# Nodo_actuador_doble.net
KiCad netlist of a schematic drawn in EAGLE
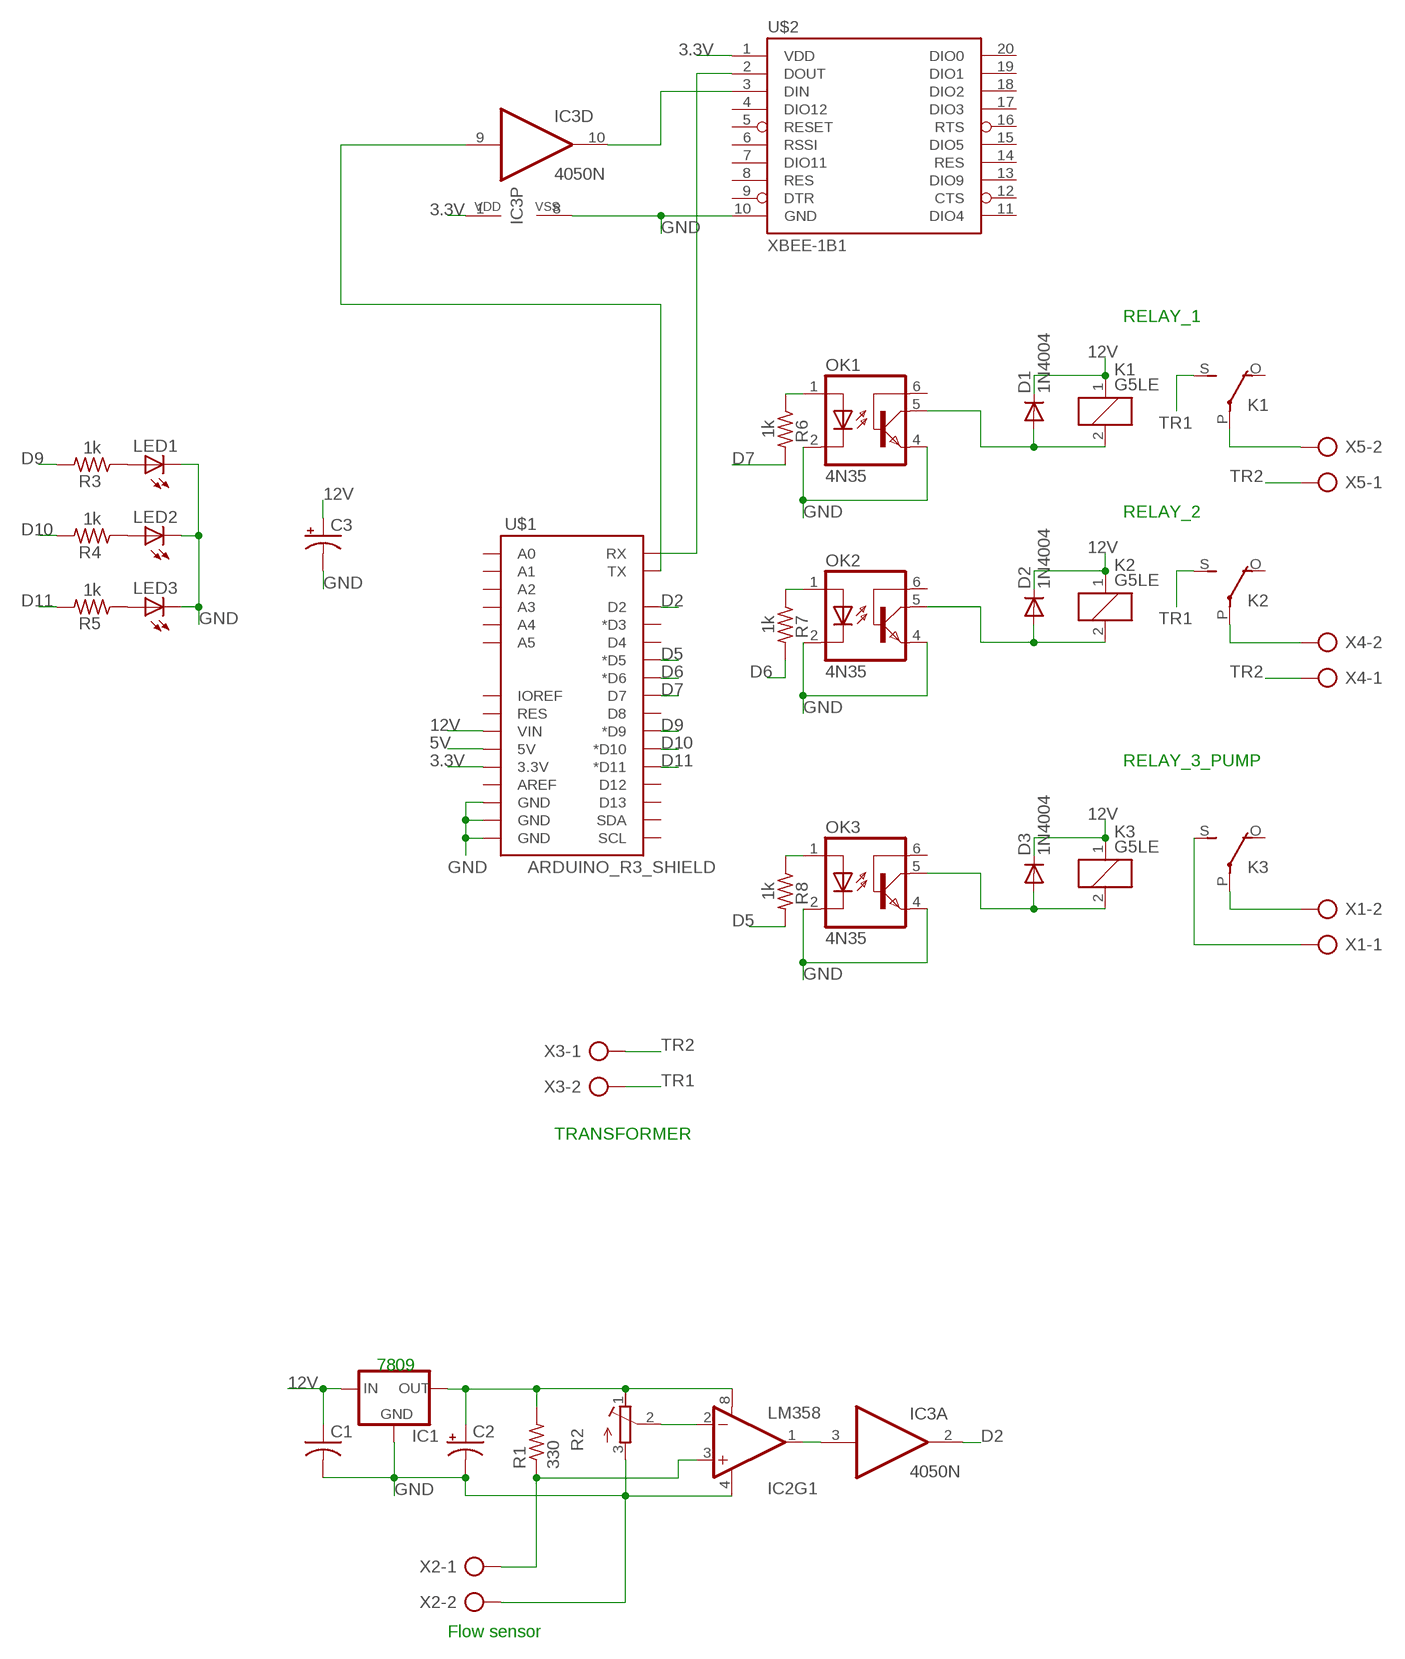
[diagram p0: schematic, sheet 1]

(export (version "E")
  (design (tool "Eeschema 10.0.6"))
  (components
    (comp (ref "C1")
      (value "C-US050-024X044")
      (footprint "eagle-import:C050-024X044")
      (libsource (lib "eagle-import") (part "C-US050-024X044"))
    )
    (comp (ref "C2")
      (value "CPOL-USE2.5-6")
      (footprint "eagle-import:E2,5-6")
      (libsource (lib "eagle-import") (part "CPOL-USE2.5-6"))
    )
    (comp (ref "C3")
      (value "CPOL-USE2.5-6")
      (footprint "eagle-import:E2,5-6")
      (libsource (lib "eagle-import") (part "CPOL-USE2.5-6"))
    )
    (comp (ref "D1")
      (value "1N4004")
      (footprint "eagle-import:DO41-10")
      (libsource (lib "eagle-import") (part "1N4004"))
    )
    (comp (ref "D2")
      (value "1N4004")
      (footprint "eagle-import:DO41-10")
      (libsource (lib "eagle-import") (part "1N4004"))
    )
    (comp (ref "D3")
      (value "1N4004")
      (footprint "eagle-import:DO41-10")
      (libsource (lib "eagle-import") (part "1N4004"))
    )
    (comp (ref "IC1")
      (value "78XXS")
      (footprint "eagle-import:78XXS")
      (libsource (lib "eagle-import") (part "78XXS"))
    )
    (comp (ref "IC2")
      (value "LM358")
      (footprint "eagle-import:DIP08")
      (libsource (lib "eagle-import") (part "LM358"))
    )
    (comp (ref "IC3")
      (value "4050N")
      (footprint "eagle-import:DIL16")
      (libsource (lib "eagle-import") (part "4050N"))
    )
    (comp (ref "K1")
      (value "G5LE")
      (footprint "eagle-import:G5LE")
      (libsource (lib "eagle-import") (part "G5LE"))
    )
    (comp (ref "K2")
      (value "G5LE")
      (footprint "eagle-import:G5LE")
      (libsource (lib "eagle-import") (part "G5LE"))
    )
    (comp (ref "K3")
      (value "G5LE")
      (footprint "eagle-import:G5LE")
      (libsource (lib "eagle-import") (part "G5LE"))
    )
    (comp (ref "LED1")
      (value "LED3MM")
      (footprint "eagle-import:LED3MM")
      (libsource (lib "eagle-import") (part "LED3MM"))
    )
    (comp (ref "LED2")
      (value "LED3MM")
      (footprint "eagle-import:LED3MM")
      (libsource (lib "eagle-import") (part "LED3MM"))
    )
    (comp (ref "LED3")
      (value "LED3MM")
      (footprint "eagle-import:LED3MM")
      (libsource (lib "eagle-import") (part "LED3MM"))
    )
    (comp (ref "OK1")
      (value "4N35")
      (footprint "eagle-import:DIL06")
      (fields (field (name "MF") "FAIRCHILD SEMICONDUCTOR"))
      (libsource (lib "eagle-import") (part "4N35"))
    )
    (comp (ref "OK2")
      (value "4N35")
      (footprint "eagle-import:DIL06")
      (fields (field (name "MF") "FAIRCHILD SEMICONDUCTOR"))
      (libsource (lib "eagle-import") (part "4N35"))
    )
    (comp (ref "OK3")
      (value "4N35")
      (footprint "eagle-import:DIL06")
      (fields (field (name "MF") "FAIRCHILD SEMICONDUCTOR"))
      (libsource (lib "eagle-import") (part "4N35"))
    )
    (comp (ref "R1")
      (value "330")
      (footprint "eagle-import:0204_7")
      (libsource (lib "eagle-import") (part "R-US_0204/7"))
    )
    (comp (ref "R2")
      (value "R-TRIMMT93YA")
      (footprint "eagle-import:RTRIMT93YA")
      (libsource (lib "eagle-import") (part "R-TRIMMT93YA"))
    )
    (comp (ref "R3")
      (value "1k")
      (footprint "eagle-import:0204_7")
      (libsource (lib "eagle-import") (part "R-US_0204/7"))
    )
    (comp (ref "R4")
      (value "1k")
      (footprint "eagle-import:0204_7")
      (libsource (lib "eagle-import") (part "R-US_0204/7"))
    )
    (comp (ref "R5")
      (value "1k")
      (footprint "eagle-import:0204_7")
      (libsource (lib "eagle-import") (part "R-US_0204/7"))
    )
    (comp (ref "R6")
      (value "1k")
      (footprint "eagle-import:0204_7")
      (libsource (lib "eagle-import") (part "R-US_0204/7"))
    )
    (comp (ref "R7")
      (value "1k")
      (footprint "eagle-import:0204_7")
      (libsource (lib "eagle-import") (part "R-US_0204/7"))
    )
    (comp (ref "R8")
      (value "1k")
      (footprint "eagle-import:0204_7")
      (libsource (lib "eagle-import") (part "R-US_0204/7"))
    )
    (comp (ref "U$1")
      (value "ARDUINO_R3_SHIELD")
      (footprint "eagle-import:UNO_R3_SHIELD")
      (libsource (lib "eagle-import") (part "ARDUINO_R3_SHIELD"))
    )
    (comp (ref "U$2")
      (value "XBEE-1B1")
      (footprint "eagle-import:XBEE-1")
      (libsource (lib "eagle-import") (part "XBEE-1B1"))
    )
    (comp (ref "X1")
      (value "AK500/2")
      (footprint "eagle-import:AK500_2")
      (libsource (lib "eagle-import") (part "AK500/2"))
    )
    (comp (ref "X2")
      (value "AK500/2")
      (footprint "eagle-import:AK500_2")
      (libsource (lib "eagle-import") (part "AK500/2"))
    )
    (comp (ref "X3")
      (value "AK500/2")
      (footprint "eagle-import:AK500_2")
      (libsource (lib "eagle-import") (part "AK500/2"))
    )
    (comp (ref "X4")
      (value "AK500/2")
      (footprint "eagle-import:AK500_2")
      (libsource (lib "eagle-import") (part "AK500/2"))
    )
    (comp (ref "X5")
      (value "AK500/2")
      (footprint "eagle-import:AK500_2")
      (libsource (lib "eagle-import") (part "AK500/2"))
    )
  )
  (nets
    (net (code "1") (name "/3.3V") (class "Default")
      (node (ref "IC3") (pin "1") (pinfunction "VDD_1") (pintype "power_in"))
      (node (ref "U$1") (pin "3.3V") (pinfunction "3.3V_3.3V") (pintype "bidirectional"))
      (node (ref "U$2") (pin "1") (pinfunction "VDD_1") (pintype "power_in"))
    )
    (net (code "2") (name "/5V") (class "Default")
      (node (ref "U$1") (pin "5V") (pinfunction "5V_5V") (pintype "bidirectional"))
    )
    (net (code "3") (name "/12V") (class "Default")
      (node (ref "C1") (pin "1") (pinfunction "1_1") (pintype "passive"))
      (node (ref "C3") (pin "+") (pinfunction "+_+") (pintype "passive"))
      (node (ref "D1") (pin "C") (pinfunction "C_C") (pintype "passive"))
      (node (ref "D2") (pin "C") (pinfunction "C_C") (pintype "passive"))
      (node (ref "D3") (pin "C") (pinfunction "C_C") (pintype "passive"))
      (node (ref "IC1") (pin "IN") (pinfunction "IN_IN") (pintype "input"))
      (node (ref "K1") (pin "1") (pinfunction "1_1") (pintype "passive"))
      (node (ref "K2") (pin "1") (pinfunction "1_1") (pintype "passive"))
      (node (ref "K3") (pin "1") (pinfunction "1_1") (pintype "passive"))
      (node (ref "U$1") (pin "VIN") (pinfunction "VIN_VIN") (pintype "bidirectional"))
    )
    (net (code "4") (name "/D2") (class "Default")
      (node (ref "IC3") (pin "2") (pinfunction "O_2") (pintype "output"))
      (node (ref "U$1") (pin "D2") (pinfunction "D2_D2") (pintype "bidirectional"))
    )
    (net (code "5") (name "/D5") (class "Default")
      (node (ref "R8") (pin "2") (pinfunction "2_2") (pintype "passive"))
      (node (ref "U$1") (pin "D5") (pinfunction "*D5_D5") (pintype "bidirectional"))
    )
    (net (code "6") (name "/D6") (class "Default")
      (node (ref "R7") (pin "2") (pinfunction "2_2") (pintype "passive"))
      (node (ref "U$1") (pin "D6") (pinfunction "*D6_D6") (pintype "bidirectional"))
    )
    (net (code "7") (name "/D7") (class "Default")
      (node (ref "R6") (pin "2") (pinfunction "2_2") (pintype "passive"))
      (node (ref "U$1") (pin "D7") (pinfunction "D7_D7") (pintype "bidirectional"))
    )
    (net (code "8") (name "/D9") (class "Default")
      (node (ref "R3") (pin "2") (pinfunction "2_2") (pintype "passive"))
      (node (ref "U$1") (pin "D9") (pinfunction "*D9_D9") (pintype "bidirectional"))
    )
    (net (code "9") (name "/D10") (class "Default")
      (node (ref "R4") (pin "2") (pinfunction "2_2") (pintype "passive"))
      (node (ref "U$1") (pin "D10") (pinfunction "*D10_D10") (pintype "bidirectional"))
    )
    (net (code "10") (name "/D11") (class "Default")
      (node (ref "R5") (pin "2") (pinfunction "2_2") (pintype "passive"))
      (node (ref "U$1") (pin "D11") (pinfunction "*D11_D11") (pintype "bidirectional"))
    )
    (net (code "11") (name "/GND") (class "Default")
      (node (ref "C1") (pin "2") (pinfunction "2_2") (pintype "passive"))
      (node (ref "C2") (pin "-") (pinfunction "-_-") (pintype "passive"))
      (node (ref "C3") (pin "-") (pinfunction "-_-") (pintype "passive"))
      (node (ref "IC1") (pin "GND") (pinfunction "GND_GND") (pintype "input"))
      (node (ref "IC2") (pin "4") (pinfunction "V-_4") (pintype "power_in"))
      (node (ref "IC3") (pin "8") (pinfunction "VSS_8") (pintype "power_in"))
      (node (ref "LED1") (pin "K") (pinfunction "C_K") (pintype "passive"))
      (node (ref "LED2") (pin "K") (pinfunction "C_K") (pintype "passive"))
      (node (ref "LED3") (pin "K") (pinfunction "C_K") (pintype "passive"))
      (node (ref "OK1") (pin "2") (pinfunction "C_2") (pintype "passive"))
      (node (ref "OK1") (pin "4") (pinfunction "EMI_4") (pintype "passive"))
      (node (ref "OK2") (pin "2") (pinfunction "C_2") (pintype "passive"))
      (node (ref "OK2") (pin "4") (pinfunction "EMI_4") (pintype "passive"))
      (node (ref "OK3") (pin "2") (pinfunction "C_2") (pintype "passive"))
      (node (ref "OK3") (pin "4") (pinfunction "EMI_4") (pintype "passive"))
      (node (ref "R2") (pin "3") (pinfunction "E_3") (pintype "passive"))
      (node (ref "U$1") (pin "GND@0") (pinfunction "GND_GND@0") (pintype "bidirectional"))
      (node (ref "U$1") (pin "GND@1") (pinfunction "GND_GND@1") (pintype "bidirectional"))
      (node (ref "U$1") (pin "GND@2") (pinfunction "GND_GND@2") (pintype "bidirectional"))
      (node (ref "U$2") (pin "10") (pinfunction "GND_10") (pintype "power_in"))
      (node (ref "X2") (pin "2") (pinfunction "KL_2") (pintype "passive"))
    )
    (net (code "12") (name "/TR1") (class "Default")
      (node (ref "K1") (pin "S") (pinfunction "S_S") (pintype "passive"))
      (node (ref "K2") (pin "S") (pinfunction "S_S") (pintype "passive"))
      (node (ref "X3") (pin "2") (pinfunction "KL_2") (pintype "passive"))
    )
    (net (code "13") (name "/TR2") (class "Default")
      (node (ref "X3") (pin "1") (pinfunction "KL_1") (pintype "passive"))
      (node (ref "X4") (pin "1") (pinfunction "KL_1") (pintype "passive"))
      (node (ref "X5") (pin "1") (pinfunction "KL_1") (pintype "passive"))
    )
    (net (code "14") (name "Net-(IC2A-+IN)") (class "Default")
      (node (ref "IC2") (pin "3") (pinfunction "+IN_3") (pintype "input"))
      (node (ref "R1") (pin "1") (pinfunction "1_1") (pintype "passive"))
      (node (ref "X2") (pin "1") (pinfunction "KL_1") (pintype "passive"))
    )
    (net (code "15") (name "Net-(IC2A--IN)") (class "Default")
      (node (ref "IC2") (pin "2") (pinfunction "-IN_2") (pintype "input"))
      (node (ref "R2") (pin "2") (pinfunction "S_2") (pintype "passive"))
    )
    (net (code "16") (name "Net-(IC2A-OUT)") (class "Default")
      (node (ref "IC2") (pin "1") (pinfunction "OUT_1") (pintype "output"))
      (node (ref "IC3") (pin "3") (pinfunction "I_3") (pintype "input"))
    )
    (net (code "17") (name "Net-(IC2A-V+)") (class "Default")
      (node (ref "C2") (pin "+") (pinfunction "+_+") (pintype "passive"))
      (node (ref "IC1") (pin "OUT") (pinfunction "OUT_OUT") (pintype "passive"))
      (node (ref "IC2") (pin "8") (pinfunction "V+_8") (pintype "power_in"))
      (node (ref "R1") (pin "2") (pinfunction "2_2") (pintype "passive"))
      (node (ref "R2") (pin "1") (pinfunction "A_1") (pintype "passive"))
    )
    (net (code "18") (name "Net-(IC3D-I)") (class "Default")
      (node (ref "IC3") (pin "9") (pinfunction "I_9") (pintype "input"))
      (node (ref "U$1") (pin "TX") (pinfunction "TX_TX") (pintype "bidirectional"))
    )
    (net (code "19") (name "Net-(IC3D-O)") (class "Default")
      (node (ref "IC3") (pin "10") (pinfunction "O_10") (pintype "output"))
      (node (ref "U$2") (pin "3") (pinfunction "DIN_3") (pintype "input"))
    )
    (net (code "20") (name "Net-(LED1-PadA)") (class "Default")
      (node (ref "LED1") (pin "A") (pinfunction "A_A") (pintype "passive"))
      (node (ref "R3") (pin "1") (pinfunction "1_1") (pintype "passive"))
    )
    (net (code "21") (name "Net-(LED2-PadA)") (class "Default")
      (node (ref "LED2") (pin "A") (pinfunction "A_A") (pintype "passive"))
      (node (ref "R4") (pin "1") (pinfunction "1_1") (pintype "passive"))
    )
    (net (code "22") (name "Net-(LED3-PadA)") (class "Default")
      (node (ref "LED3") (pin "A") (pinfunction "A_A") (pintype "passive"))
      (node (ref "R5") (pin "1") (pinfunction "1_1") (pintype "passive"))
    )
    (net (code "23") (name "Net-(OK1-A)") (class "Default")
      (node (ref "OK1") (pin "1") (pinfunction "A_1") (pintype "passive"))
      (node (ref "R6") (pin "1") (pinfunction "1_1") (pintype "passive"))
    )
    (net (code "24") (name "Net-(OK1-COL)") (class "Default")
      (node (ref "D1") (pin "A") (pinfunction "A_A") (pintype "passive"))
      (node (ref "K1") (pin "2") (pinfunction "2_2") (pintype "passive"))
      (node (ref "OK1") (pin "5") (pinfunction "COL_5") (pintype "passive"))
    )
    (net (code "25") (name "Net-(OK2-A)") (class "Default")
      (node (ref "OK2") (pin "1") (pinfunction "A_1") (pintype "passive"))
      (node (ref "R7") (pin "1") (pinfunction "1_1") (pintype "passive"))
    )
    (net (code "26") (name "Net-(OK2-COL)") (class "Default")
      (node (ref "D2") (pin "A") (pinfunction "A_A") (pintype "passive"))
      (node (ref "K2") (pin "2") (pinfunction "2_2") (pintype "passive"))
      (node (ref "OK2") (pin "5") (pinfunction "COL_5") (pintype "passive"))
    )
    (net (code "27") (name "Net-(OK3-A)") (class "Default")
      (node (ref "OK3") (pin "1") (pinfunction "A_1") (pintype "passive"))
      (node (ref "R8") (pin "1") (pinfunction "1_1") (pintype "passive"))
    )
    (net (code "28") (name "Net-(OK3-COL)") (class "Default")
      (node (ref "D3") (pin "A") (pinfunction "A_A") (pintype "passive"))
      (node (ref "K3") (pin "2") (pinfunction "2_2") (pintype "passive"))
      (node (ref "OK3") (pin "5") (pinfunction "COL_5") (pintype "passive"))
    )
    (net (code "29") (name "Net-(U$2-DOUT)") (class "Default")
      (node (ref "U$1") (pin "RX") (pinfunction "RX_RX") (pintype "bidirectional"))
      (node (ref "U$2") (pin "2") (pinfunction "DOUT_2") (pintype "output"))
    )
    (net (code "30") (name "Net-(X1A-KL)") (class "Default")
      (node (ref "K3") (pin "S") (pinfunction "S_S") (pintype "passive"))
      (node (ref "X1") (pin "1") (pinfunction "KL_1") (pintype "passive"))
    )
    (net (code "31") (name "Net-(X1B-KL)") (class "Default")
      (node (ref "K3") (pin "P") (pinfunction "P_P") (pintype "passive"))
      (node (ref "X1") (pin "2") (pinfunction "KL_2") (pintype "passive"))
    )
    (net (code "32") (name "Net-(X4B-KL)") (class "Default")
      (node (ref "K2") (pin "P") (pinfunction "P_P") (pintype "passive"))
      (node (ref "X4") (pin "2") (pinfunction "KL_2") (pintype "passive"))
    )
    (net (code "33") (name "Net-(X5B-KL)") (class "Default")
      (node (ref "K1") (pin "P") (pinfunction "P_P") (pintype "passive"))
      (node (ref "X5") (pin "2") (pinfunction "KL_2") (pintype "passive"))
    )
    (net (code "34") (name "unconnected-(K1-PadO)") (class "Default")
      (node (ref "K1") (pin "O") (pinfunction "O_O") (pintype "passive"))
    )
    (net (code "35") (name "unconnected-(K2-PadO)") (class "Default")
      (node (ref "K2") (pin "O") (pinfunction "O_O") (pintype "passive"))
    )
    (net (code "36") (name "unconnected-(K3-PadO)") (class "Default")
      (node (ref "K3") (pin "O") (pinfunction "O_O") (pintype "passive"))
    )
    (net (code "37") (name "unconnected-(OK1-BAS-Pad6)") (class "Default")
      (node (ref "OK1") (pin "6") (pinfunction "BAS_6") (pintype "passive"))
    )
    (net (code "38") (name "unconnected-(OK2-BAS-Pad6)") (class "Default")
      (node (ref "OK2") (pin "6") (pinfunction "BAS_6") (pintype "passive"))
    )
    (net (code "39") (name "unconnected-(OK3-BAS-Pad6)") (class "Default")
      (node (ref "OK3") (pin "6") (pinfunction "BAS_6") (pintype "passive"))
    )
    (net (code "40") (name "unconnected-(U$1-*D3-PadD3)") (class "Default")
      (node (ref "U$1") (pin "D3") (pinfunction "*D3_D3") (pintype "bidirectional"))
    )
    (net (code "41") (name "unconnected-(U$1-PadA0)") (class "Default")
      (node (ref "U$1") (pin "A0") (pinfunction "A0_A0") (pintype "bidirectional"))
    )
    (net (code "42") (name "unconnected-(U$1-PadA1)") (class "Default")
      (node (ref "U$1") (pin "A1") (pinfunction "A1_A1") (pintype "bidirectional"))
    )
    (net (code "43") (name "unconnected-(U$1-PadA2)") (class "Default")
      (node (ref "U$1") (pin "A2") (pinfunction "A2_A2") (pintype "bidirectional"))
    )
    (net (code "44") (name "unconnected-(U$1-PadA3)") (class "Default")
      (node (ref "U$1") (pin "A3") (pinfunction "A3_A3") (pintype "bidirectional"))
    )
    (net (code "45") (name "unconnected-(U$1-PadA4)") (class "Default")
      (node (ref "U$1") (pin "A4") (pinfunction "A4_A4") (pintype "bidirectional"))
    )
    (net (code "46") (name "unconnected-(U$1-PadA5)") (class "Default")
      (node (ref "U$1") (pin "A5") (pinfunction "A5_A5") (pintype "bidirectional"))
    )
    (net (code "47") (name "unconnected-(U$1-PadAREF)") (class "Default")
      (node (ref "U$1") (pin "AREF") (pinfunction "AREF_AREF") (pintype "bidirectional"))
    )
    (net (code "48") (name "unconnected-(U$1-PadD4)") (class "Default")
      (node (ref "U$1") (pin "D4") (pinfunction "D4_D4") (pintype "bidirectional"))
    )
    (net (code "49") (name "unconnected-(U$1-PadD8)") (class "Default")
      (node (ref "U$1") (pin "D8") (pinfunction "D8_D8") (pintype "bidirectional"))
    )
    (net (code "50") (name "unconnected-(U$1-PadD12)") (class "Default")
      (node (ref "U$1") (pin "D12") (pinfunction "D12_D12") (pintype "bidirectional"))
    )
    (net (code "51") (name "unconnected-(U$1-PadD13)") (class "Default")
      (node (ref "U$1") (pin "D13") (pinfunction "D13_D13") (pintype "bidirectional"))
    )
    (net (code "52") (name "unconnected-(U$1-PadIOREF)") (class "Default")
      (node (ref "U$1") (pin "IOREF") (pinfunction "IOREF_IOREF") (pintype "bidirectional"))
    )
    (net (code "53") (name "unconnected-(U$1-PadRES)") (class "Default")
      (node (ref "U$1") (pin "RES") (pinfunction "RES_RES") (pintype "bidirectional"))
    )
    (net (code "54") (name "unconnected-(U$1-PadSCL)") (class "Default")
      (node (ref "U$1") (pin "SCL") (pinfunction "SCL_SCL") (pintype "bidirectional"))
    )
    (net (code "55") (name "unconnected-(U$1-PadSDA)") (class "Default")
      (node (ref "U$1") (pin "SDA") (pinfunction "SDA_SDA") (pintype "bidirectional"))
    )
    (net (code "56") (name "unconnected-(U$2-CTS-Pad12)") (class "Default")
      (node (ref "U$2") (pin "12") (pinfunction "CTS_12") (pintype "output"))
    )
    (net (code "57") (name "unconnected-(U$2-DIO0-Pad20)") (class "Default")
      (node (ref "U$2") (pin "20") (pinfunction "DIO0_20") (pintype "bidirectional"))
    )
    (net (code "58") (name "unconnected-(U$2-DIO1-Pad19)") (class "Default")
      (node (ref "U$2") (pin "19") (pinfunction "DIO1_19") (pintype "bidirectional"))
    )
    (net (code "59") (name "unconnected-(U$2-DIO2-Pad18)") (class "Default")
      (node (ref "U$2") (pin "18") (pinfunction "DIO2_18") (pintype "bidirectional"))
    )
    (net (code "60") (name "unconnected-(U$2-DIO3-Pad17)") (class "Default")
      (node (ref "U$2") (pin "17") (pinfunction "DIO3_17") (pintype "bidirectional"))
    )
    (net (code "61") (name "unconnected-(U$2-DIO4-Pad11)") (class "Default")
      (node (ref "U$2") (pin "11") (pinfunction "DIO4_11") (pintype "bidirectional"))
    )
    (net (code "62") (name "unconnected-(U$2-DIO5-Pad15)") (class "Default")
      (node (ref "U$2") (pin "15") (pinfunction "DIO5_15") (pintype "bidirectional"))
    )
    (net (code "63") (name "unconnected-(U$2-DIO9-Pad13)") (class "Default")
      (node (ref "U$2") (pin "13") (pinfunction "DIO9_13") (pintype "bidirectional"))
    )
    (net (code "64") (name "unconnected-(U$2-DIO11-Pad7)") (class "Default")
      (node (ref "U$2") (pin "7") (pinfunction "DIO11_7") (pintype "bidirectional"))
    )
    (net (code "65") (name "unconnected-(U$2-DIO12-Pad4)") (class "Default")
      (node (ref "U$2") (pin "4") (pinfunction "DIO12_4") (pintype "bidirectional"))
    )
    (net (code "66") (name "unconnected-(U$2-DTR-Pad9)") (class "Default")
      (node (ref "U$2") (pin "9") (pinfunction "DTR_9") (pintype "bidirectional"))
    )
    (net (code "67") (name "unconnected-(U$2-RES-Pad8)") (class "Default")
      (node (ref "U$2") (pin "8") (pinfunction "RES_8") (pintype "bidirectional"))
    )
    (net (code "68") (name "unconnected-(U$2-RES-Pad14)") (class "Default")
      (node (ref "U$2") (pin "14") (pinfunction "RES_14") (pintype "bidirectional"))
    )
    (net (code "69") (name "unconnected-(U$2-RESET-Pad5)") (class "Default")
      (node (ref "U$2") (pin "5") (pinfunction "RESET_5") (pintype "input"))
    )
    (net (code "70") (name "unconnected-(U$2-RSSI-Pad6)") (class "Default")
      (node (ref "U$2") (pin "6") (pinfunction "RSSI_6") (pintype "bidirectional"))
    )
    (net (code "71") (name "unconnected-(U$2-RTS-Pad16)") (class "Default")
      (node (ref "U$2") (pin "16") (pinfunction "RTS_16") (pintype "input"))
    )
  )
)
